# flash.net
KiCad netlist of a schematic drawn in Altium Designer
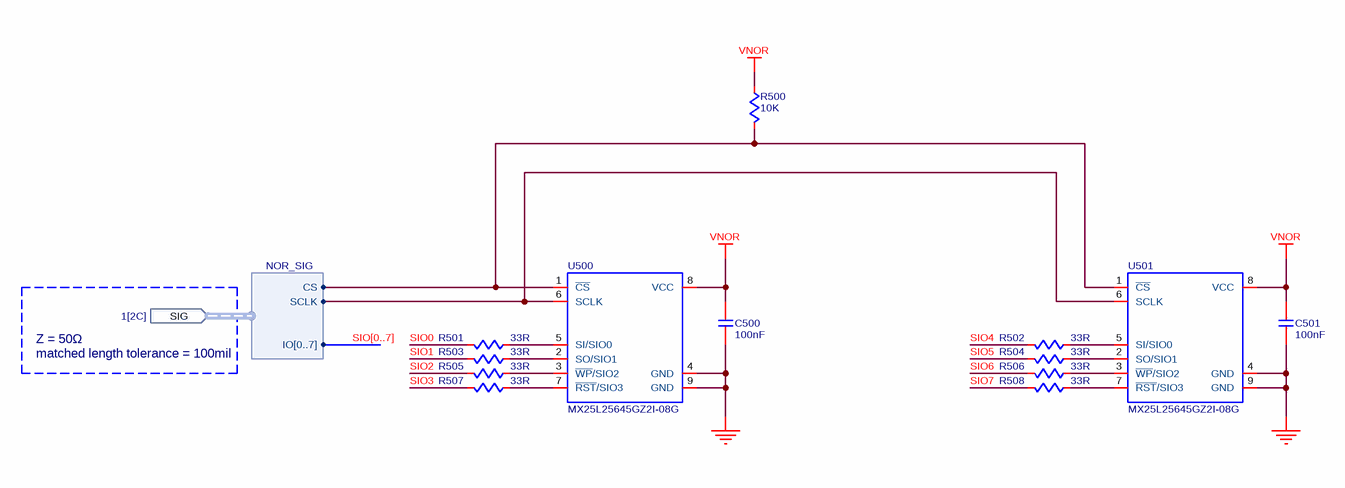
[diagram p0: flash.schdoc]

(export (version "E")
  (design (tool "Eeschema 10.0.6"))
  (components
    (comp (ref "C500")
      (value "100nF")
      (footprint "mw:C0402")
      (fields (field (name "VOLTAGE") "25V") (field (name "Comment") "C-NOMO"))
      (libsource (lib "mw") (part "C-NOMO"))
    )
    (comp (ref "C501")
      (value "100nF")
      (footprint "mw:C0402")
      (fields (field (name "VOLTAGE") "25V") (field (name "Comment") "C-NOMO"))
      (libsource (lib "mw") (part "C-NOMO"))
    )
    (comp (ref "R500")
      (value "10K")
      (footprint "mw:R0402")
      (fields (field (name "Comment") "R"))
      (libsource (lib "mw") (part "R"))
    )
    (comp (ref "R501")
      (value "33R")
      (footprint "mw:R0402")
      (fields (field (name "Comment") "R"))
      (libsource (lib "mw") (part "R"))
    )
    (comp (ref "R502")
      (value "33R")
      (footprint "mw:R0402")
      (fields (field (name "Comment") "R"))
      (libsource (lib "mw") (part "R"))
    )
    (comp (ref "R503")
      (value "33R")
      (footprint "mw:R0402")
      (fields (field (name "Comment") "R"))
      (libsource (lib "mw") (part "R"))
    )
    (comp (ref "R504")
      (value "33R")
      (footprint "mw:R0402")
      (fields (field (name "Comment") "R"))
      (libsource (lib "mw") (part "R"))
    )
    (comp (ref "R505")
      (value "33R")
      (footprint "mw:R0402")
      (fields (field (name "Comment") "R"))
      (libsource (lib "mw") (part "R"))
    )
    (comp (ref "R506")
      (value "33R")
      (footprint "mw:R0402")
      (fields (field (name "Comment") "R"))
      (libsource (lib "mw") (part "R"))
    )
    (comp (ref "R507")
      (value "33R")
      (footprint "mw:R0402")
      (fields (field (name "Comment") "R"))
      (libsource (lib "mw") (part "R"))
    )
    (comp (ref "R508")
      (value "33R")
      (footprint "mw:R0402")
      (fields (field (name "Comment") "R"))
      (libsource (lib "mw") (part "R"))
    )
    (comp (ref "U500")
      (value "MX25L25645GZ2I-08G")
      (footprint "MX25L25645GZ2I-08G")
      (libsource (lib "mw") (part "MX25L25645GZ2I-08G"))
    )
    (comp (ref "U501")
      (value "MX25L25645GZ2I-08G")
      (footprint "MX25L25645GZ2I-08G")
      (libsource (lib "mw") (part "MX25L25645GZ2I-08G"))
    )
  )
  (nets
    (net (code "2") (name "/SIO0") (class "Default")
      (node (ref "R501") (pin "1") (pinfunction "1_1") (pintype "passive"))
    )
    (net (code "3") (name "/SIO1") (class "Default")
      (node (ref "R503") (pin "1") (pinfunction "1_1") (pintype "passive"))
    )
    (net (code "4") (name "/SIO2") (class "Default")
      (node (ref "R505") (pin "1") (pinfunction "1_1") (pintype "passive"))
    )
    (net (code "5") (name "/SIO3") (class "Default")
      (node (ref "R507") (pin "1") (pinfunction "1_1") (pintype "passive"))
    )
    (net (code "6") (name "/SIO4") (class "Default")
      (node (ref "R502") (pin "1") (pinfunction "1_1") (pintype "passive"))
    )
    (net (code "7") (name "/SIO5") (class "Default")
      (node (ref "R504") (pin "1") (pinfunction "1_1") (pintype "passive"))
    )
    (net (code "8") (name "/SIO6") (class "Default")
      (node (ref "R506") (pin "1") (pinfunction "1_1") (pintype "passive"))
    )
    (net (code "9") (name "/SIO7") (class "Default")
      (node (ref "R508") (pin "1") (pinfunction "1_1") (pintype "passive"))
    )
    (net (code "12") (name "GND") (class "Default")
      (node (ref "C500") (pin "1") (pinfunction "1_1") (pintype "passive"))
      (node (ref "C501") (pin "1") (pinfunction "1_1") (pintype "passive"))
      (node (ref "U500") (pin "4") (pinfunction "GND_4") (pintype "passive"))
      (node (ref "U500") (pin "9") (pinfunction "GND_9") (pintype "passive"))
      (node (ref "U501") (pin "4") (pinfunction "GND_4") (pintype "passive"))
      (node (ref "U501") (pin "9") (pinfunction "GND_9") (pintype "passive"))
    )
    (net (code "13") (name "Net-(U500-SCLK)") (class "Default")
      (node (ref "U500") (pin "6") (pinfunction "SCLK_6") (pintype "passive"))
      (node (ref "U501") (pin "6") (pinfunction "SCLK_6") (pintype "passive"))
    )
    (net (code "14") (name "Net-(U500-SI{slash}SIO0)") (class "Default")
      (node (ref "R501") (pin "2") (pinfunction "2_2") (pintype "passive"))
      (node (ref "U500") (pin "5") (pinfunction "SI/SIO0_5") (pintype "passive"))
    )
    (net (code "15") (name "Net-(U500-SO{slash}SIO1)") (class "Default")
      (node (ref "R503") (pin "2") (pinfunction "2_2") (pintype "passive"))
      (node (ref "U500") (pin "2") (pinfunction "SO/SIO1_2") (pintype "passive"))
    )
    (net (code "16") (name "Net-(U500-~{CS})") (class "Default")
      (node (ref "R500") (pin "1") (pinfunction "1_1") (pintype "passive"))
      (node (ref "U500") (pin "1") (pinfunction "~{CS}_1") (pintype "passive"))
      (node (ref "U501") (pin "1") (pinfunction "~{CS}_1") (pintype "passive"))
    )
    (net (code "17") (name "Net-(U500-~{RST}{slash}SIO3)") (class "Default")
      (node (ref "R507") (pin "2") (pinfunction "2_2") (pintype "passive"))
      (node (ref "U500") (pin "7") (pinfunction "~{RST}/SIO3_7") (pintype "passive"))
    )
    (net (code "18") (name "Net-(U500-~{WP}{slash}SIO2)") (class "Default")
      (node (ref "R505") (pin "2") (pinfunction "2_2") (pintype "passive"))
      (node (ref "U500") (pin "3") (pinfunction "~{WP}/SIO2_3") (pintype "passive"))
    )
    (net (code "19") (name "Net-(U501-SI{slash}SIO0)") (class "Default")
      (node (ref "R502") (pin "2") (pinfunction "2_2") (pintype "passive"))
      (node (ref "U501") (pin "5") (pinfunction "SI/SIO0_5") (pintype "passive"))
    )
    (net (code "20") (name "Net-(U501-SO{slash}SIO1)") (class "Default")
      (node (ref "R504") (pin "2") (pinfunction "2_2") (pintype "passive"))
      (node (ref "U501") (pin "2") (pinfunction "SO/SIO1_2") (pintype "passive"))
    )
    (net (code "21") (name "Net-(U501-~{RST}{slash}SIO3)") (class "Default")
      (node (ref "R508") (pin "2") (pinfunction "2_2") (pintype "passive"))
      (node (ref "U501") (pin "7") (pinfunction "~{RST}/SIO3_7") (pintype "passive"))
    )
    (net (code "22") (name "Net-(U501-~{WP}{slash}SIO2)") (class "Default")
      (node (ref "R506") (pin "2") (pinfunction "2_2") (pintype "passive"))
      (node (ref "U501") (pin "3") (pinfunction "~{WP}/SIO2_3") (pintype "passive"))
    )
    (net (code "23") (name "VNOR") (class "Default")
      (node (ref "C500") (pin "2") (pinfunction "2_2") (pintype "passive"))
      (node (ref "C501") (pin "2") (pinfunction "2_2") (pintype "passive"))
      (node (ref "R500") (pin "2") (pinfunction "2_2") (pintype "passive"))
      (node (ref "U500") (pin "8") (pinfunction "VCC_8") (pintype "passive"))
      (node (ref "U501") (pin "8") (pinfunction "VCC_8") (pintype "passive"))
    )
  )
)
